# ETR_CELLMETER_MASTER.net
KiCad netlist of a schematic drawn in Altium Designer
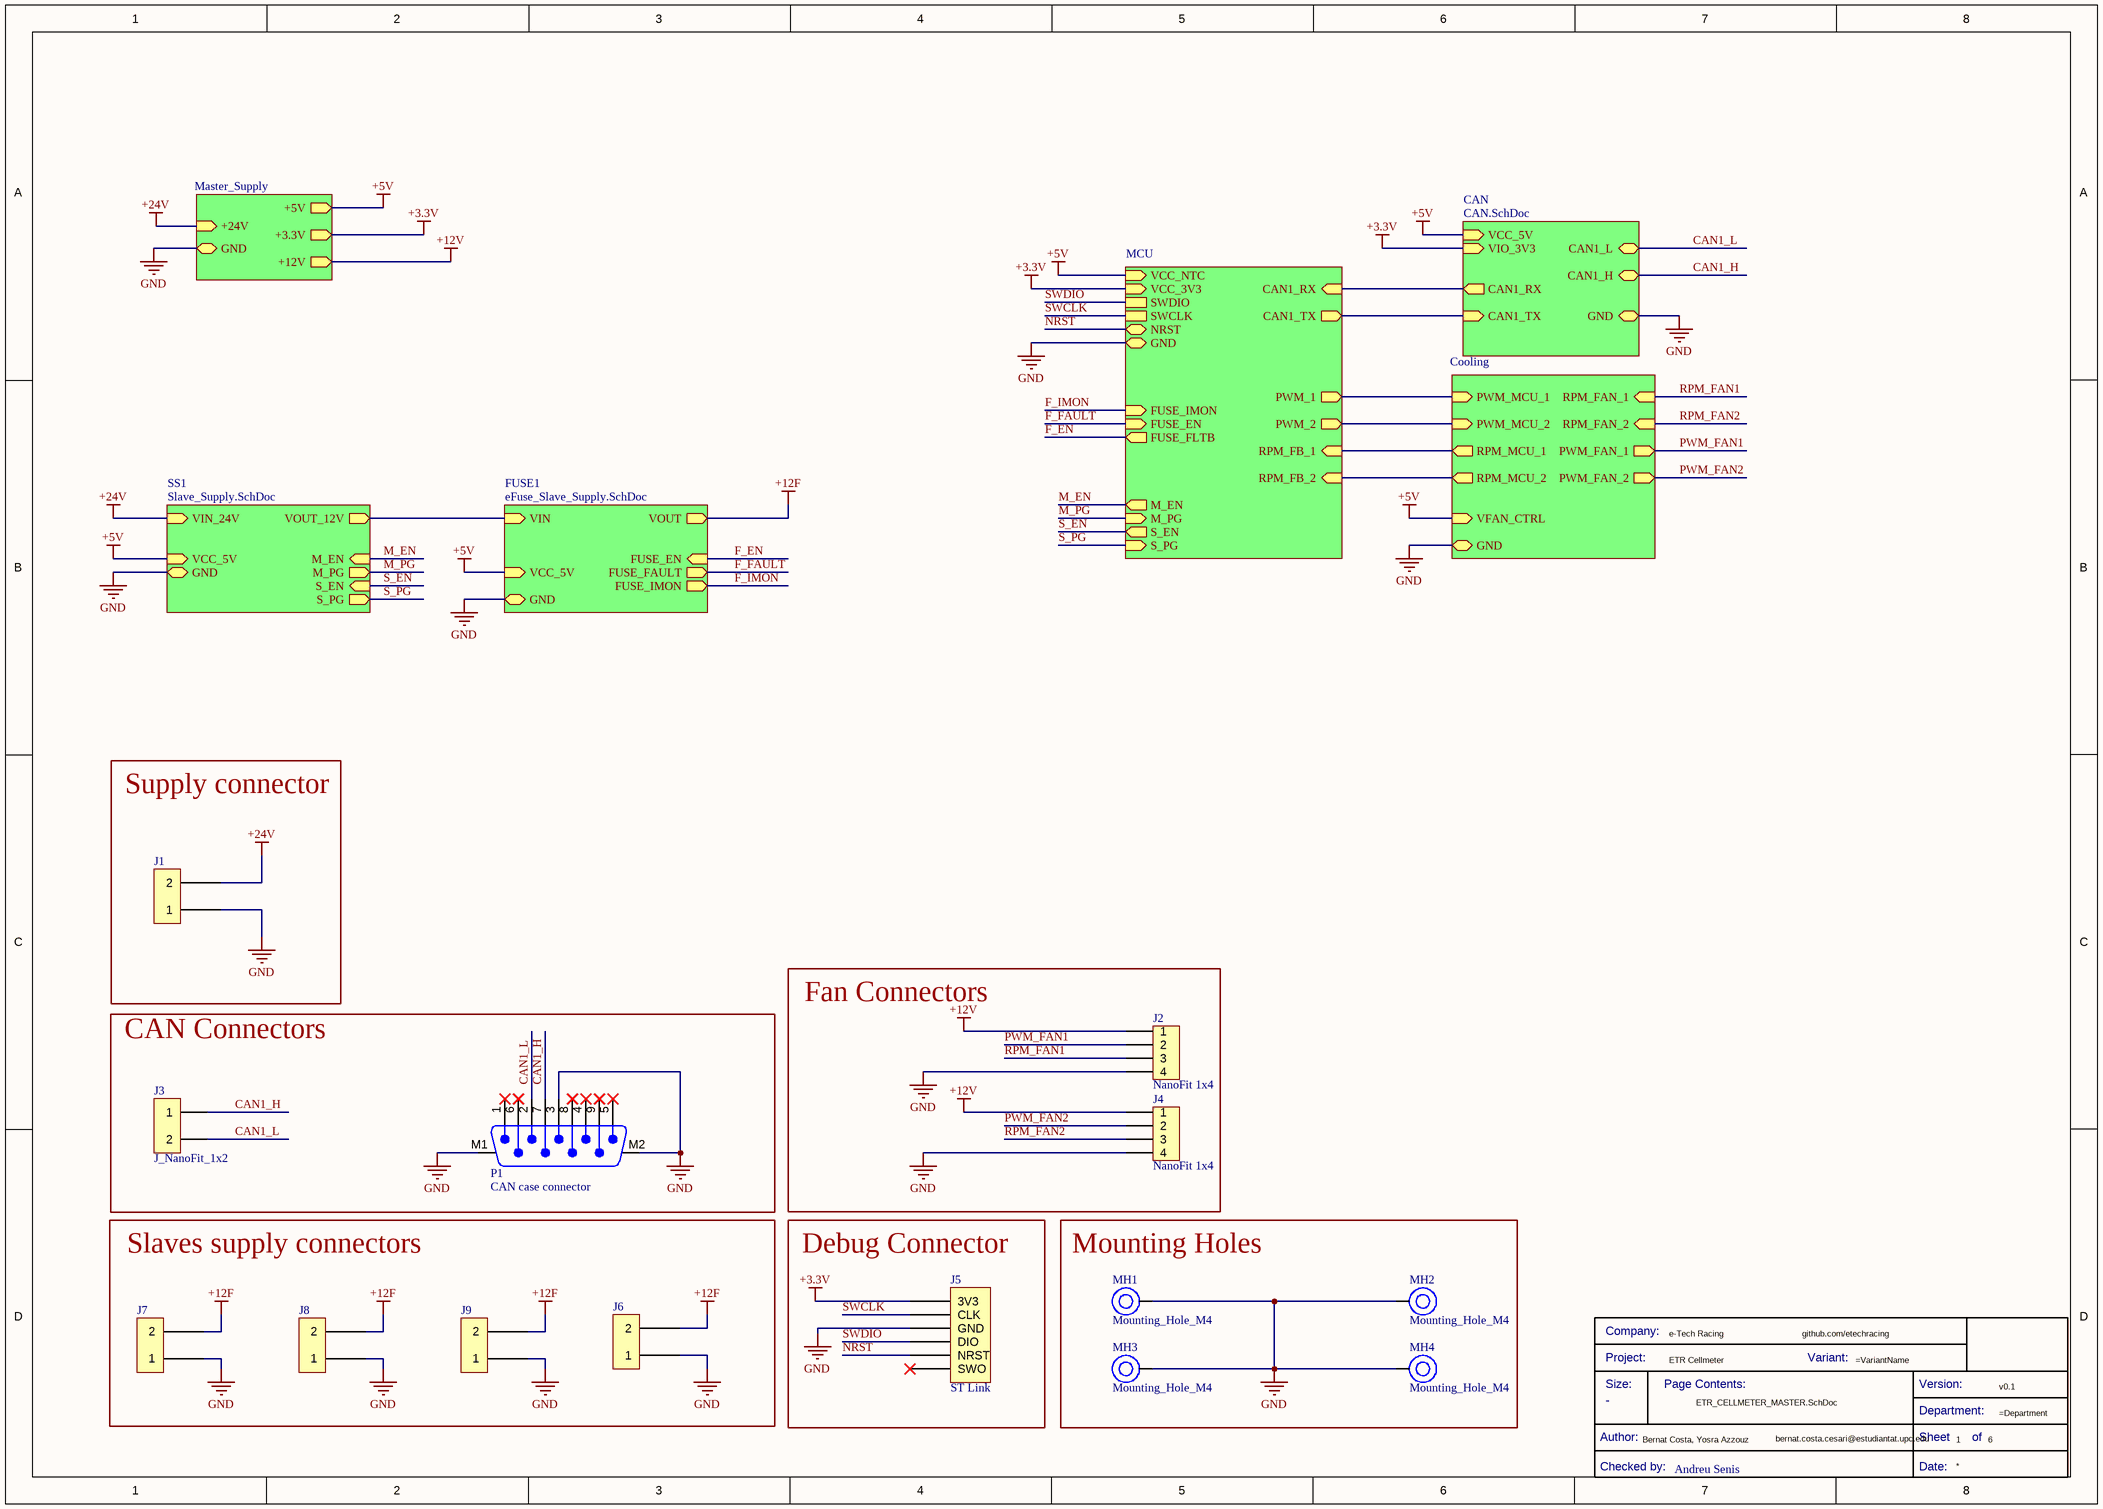
[diagram p0: ETR_CELLMETER_MASTER.SchDoc]

(export (version "E")
  (design (tool "Eeschema 10.0.6"))
  (components
    (comp (ref "J1")
      (value "J_2x1_14A_TE")
      (footprint "179838-2")
      (description "179838-2")
      (libsource (lib "EMEA- E-Tech Racing- I'Escola d'Enginyeria de Barcelona Est") (part "Power 2 pin connector"))
    )
    (comp (ref "J2")
      (value "NanoFit 1x4")
      (footprint "J_NanoFit_1x4_V")
      (description "Conn HDR 4 POS 2.5mm Solder ST Thru-Hole 4 Terminal 1 Port Nano-Fit Tray")
      (fields (field (name ".CREATOR") "DR"))
      (libsource (lib "EMEA- E-Tech Racing- I'Escola d'Enginyeria de Barcelona Est") (part "J_NanoFit_1x4_V_W"))
    )
    (comp (ref "J3")
      (value "J_NanoFit_1x2")
      (footprint "FP-105309-1102-MFG")
      (description "Conn HDR 2 POS 2.5mm Solder ST Thru-Hole 2 Terminal 1 Port Nano-Fit Tray")
      (libsource (lib "EMEA- E-Tech Racing- I'Escola d'Enginyeria de Barcelona Est") (part "Molex Nano-Fit"))
    )
    (comp (ref "J4")
      (value "NanoFit 1x4")
      (footprint "J_NanoFit_1x4_V")
      (description "Conn HDR 4 POS 2.5mm Solder ST Thru-Hole 4 Terminal 1 Port Nano-Fit Tray")
      (fields (field (name ".CREATOR") "DR"))
      (libsource (lib "EMEA- E-Tech Racing- I'Escola d'Enginyeria de Barcelona Est") (part "J_NanoFit_1x4_V_W"))
    )
    (comp (ref "J5")
      (value "ST Link")
      (footprint "J_STLink_PinHeader")
      (libsource (lib "Electromechanical") (part "J_STLink_STM32_PinHeader_1x6"))
    )
    (comp (ref "J6")
      (value "J_2x1_14A_TE")
      (footprint "179838-2")
      (description "179838-2")
      (libsource (lib "EMEA- E-Tech Racing- I'Escola d'Enginyeria de Barcelona Est") (part "Power 2 pin connector"))
    )
    (comp (ref "J7")
      (value "J_2x1_14A_TE")
      (footprint "179838-2")
      (description "179838-2")
      (libsource (lib "EMEA- E-Tech Racing- I'Escola d'Enginyeria de Barcelona Est") (part "Power 2 pin connector"))
    )
    (comp (ref "J8")
      (value "J_2x1_14A_TE")
      (footprint "179838-2")
      (description "179838-2")
      (libsource (lib "EMEA- E-Tech Racing- I'Escola d'Enginyeria de Barcelona Est") (part "Power 2 pin connector"))
    )
    (comp (ref "J9")
      (value "J_2x1_14A_TE")
      (footprint "179838-2")
      (description "179838-2")
      (libsource (lib "EMEA- E-Tech Racing- I'Escola d'Enginyeria de Barcelona Est") (part "Power 2 pin connector"))
    )
    (comp (ref "MH1")
      (value "Mounting_Hole_M4")
      (footprint "Mounting_Hole_M4")
      (description "Mounting Hole M4")
      (libsource (lib "EMEA- E-Tech Racing- I'Escola d'Enginyeria de Barcelona Est") (part "Mounting_Hole_M4"))
    )
    (comp (ref "MH2")
      (value "Mounting_Hole_M4")
      (footprint "Mounting_Hole_M4")
      (description "Mounting Hole M4")
      (libsource (lib "EMEA- E-Tech Racing- I'Escola d'Enginyeria de Barcelona Est") (part "Mounting_Hole_M4"))
    )
    (comp (ref "MH3")
      (value "Mounting_Hole_M4")
      (footprint "Mounting_Hole_M4")
      (description "Mounting Hole M4")
      (libsource (lib "EMEA- E-Tech Racing- I'Escola d'Enginyeria de Barcelona Est") (part "Mounting_Hole_M4"))
    )
    (comp (ref "MH4")
      (value "Mounting_Hole_M4")
      (footprint "Mounting_Hole_M4")
      (description "Mounting Hole M4")
      (libsource (lib "EMEA- E-Tech Racing- I'Escola d'Enginyeria de Barcelona Est") (part "Mounting_Hole_M4"))
    )
    (comp (ref "P1")
      (value "CAN case connector")
      (footprint "618009231221")
      (description "D Type Connector, 9 Contact(s), Male, Solder Terminal, Locking, Receptacle")
      (libsource (lib "EMEA- E-Tech Racing- I'Escola d'Enginyeria de Barcelona Est") (part "D-Sub_Male_09p"))
    )
  )
  (nets
    (net (code "1") (name "+3.3V") (class "Default")
      (node (ref "J5") (pin "1") (pinfunction "3V3_1") (pintype "passive"))
    )
    (net (code "3") (name "+12F") (class "Default")
      (node (ref "J6") (pin "2") (pinfunction "2_2") (pintype "passive"))
      (node (ref "J7") (pin "2") (pinfunction "2_2") (pintype "passive"))
      (node (ref "J8") (pin "2") (pinfunction "2_2") (pintype "passive"))
      (node (ref "J9") (pin "2") (pinfunction "2_2") (pintype "passive"))
    )
    (net (code "4") (name "+12V") (class "Default")
      (node (ref "J2") (pin "1") (pinfunction "1_1") (pintype "passive"))
      (node (ref "J4") (pin "1") (pinfunction "1_1") (pintype "passive"))
    )
    (net (code "5") (name "+24V") (class "Default")
      (node (ref "J1") (pin "2") (pinfunction "2_2") (pintype "passive"))
    )
    (net (code "6") (name "/CAN1_H") (class "Default")
      (node (ref "J3") (pin "1") (pinfunction "1_1") (pintype "passive"))
      (node (ref "P1") (pin "7") (pinfunction "7_7") (pintype "passive"))
    )
    (net (code "7") (name "/CAN1_L") (class "Default")
      (node (ref "J3") (pin "2") (pinfunction "2_2") (pintype "passive"))
      (node (ref "P1") (pin "2") (pinfunction "2_2") (pintype "passive"))
    )
    (net (code "15") (name "/NRST") (class "Default")
      (node (ref "J5") (pin "5") (pinfunction "NRST_5") (pintype "passive"))
    )
    (net (code "18") (name "/PWM_FAN1") (class "Default")
      (node (ref "J2") (pin "2") (pinfunction "2_2") (pintype "passive"))
    )
    (net (code "19") (name "/PWM_FAN2") (class "Default")
      (node (ref "J4") (pin "2") (pinfunction "2_2") (pintype "passive"))
    )
    (net (code "20") (name "/RPM_FAN1") (class "Default")
      (node (ref "J2") (pin "3") (pinfunction "3_3") (pintype "passive"))
    )
    (net (code "21") (name "/RPM_FAN2") (class "Default")
      (node (ref "J4") (pin "3") (pinfunction "3_3") (pintype "passive"))
    )
    (net (code "24") (name "/SWCLK") (class "Default")
      (node (ref "J5") (pin "2") (pinfunction "CLK_2") (pintype "passive"))
    )
    (net (code "25") (name "/SWDIO") (class "Default")
      (node (ref "J5") (pin "4") (pinfunction "DIO_4") (pintype "passive"))
    )
    (net (code "29") (name "GND") (class "Default")
      (node (ref "J1") (pin "1") (pinfunction "1_1") (pintype "passive"))
      (node (ref "J2") (pin "4") (pinfunction "4_4") (pintype "passive"))
      (node (ref "J4") (pin "4") (pinfunction "4_4") (pintype "passive"))
      (node (ref "J5") (pin "3") (pinfunction "GND_3") (pintype "passive"))
      (node (ref "J6") (pin "1") (pinfunction "1_1") (pintype "passive"))
      (node (ref "J7") (pin "1") (pinfunction "1_1") (pintype "passive"))
      (node (ref "J8") (pin "1") (pinfunction "1_1") (pintype "passive"))
      (node (ref "J9") (pin "1") (pinfunction "1_1") (pintype "passive"))
      (node (ref "MH1") (pin "1") (pinfunction "1_1") (pintype "passive"))
      (node (ref "MH2") (pin "1") (pinfunction "1_1") (pintype "passive"))
      (node (ref "MH3") (pin "1") (pinfunction "1_1") (pintype "passive"))
      (node (ref "MH4") (pin "1") (pinfunction "1_1") (pintype "passive"))
      (node (ref "P1") (pin "3") (pinfunction "3_3") (pintype "passive"))
      (node (ref "P1") (pin "M1") (pinfunction "M1_M1") (pintype "passive"))
      (node (ref "P1") (pin "M2") (pinfunction "M2_M2") (pintype "passive"))
    )
    (net (code "30") (name "unconnected-(J5-SWO-Pad6)") (class "Default")
      (node (ref "J5") (pin "6") (pinfunction "SWO_6") (pintype "passive+no_connect"))
    )
    (net (code "31") (name "unconnected-(P1-Pad1)") (class "Default")
      (node (ref "P1") (pin "1") (pinfunction "1_1") (pintype "passive+no_connect"))
    )
    (net (code "32") (name "unconnected-(P1-Pad4)") (class "Default")
      (node (ref "P1") (pin "4") (pinfunction "4_4") (pintype "passive+no_connect"))
    )
    (net (code "33") (name "unconnected-(P1-Pad5)") (class "Default")
      (node (ref "P1") (pin "5") (pinfunction "5_5") (pintype "passive+no_connect"))
    )
    (net (code "34") (name "unconnected-(P1-Pad6)") (class "Default")
      (node (ref "P1") (pin "6") (pinfunction "6_6") (pintype "passive+no_connect"))
    )
    (net (code "35") (name "unconnected-(P1-Pad8)") (class "Default")
      (node (ref "P1") (pin "8") (pinfunction "8_8") (pintype "passive+no_connect"))
    )
    (net (code "36") (name "unconnected-(P1-Pad9)") (class "Default")
      (node (ref "P1") (pin "9") (pinfunction "9_9") (pintype "passive+no_connect"))
    )
  )
)
